# tastatur.net
KiCad netlist of a schematic drawn in EAGLE
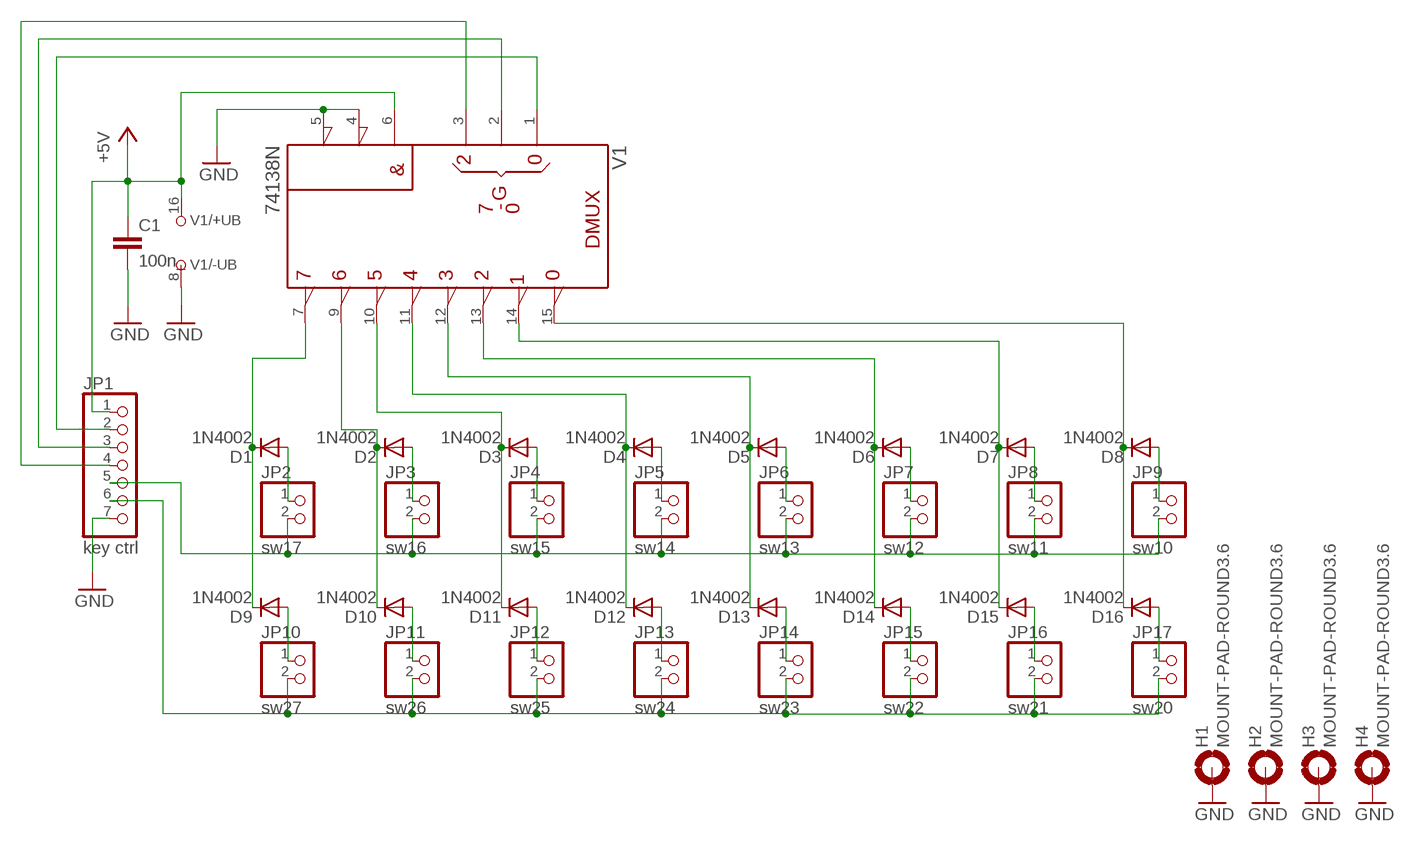
[diagram p0: schematic, sheet 1]

(export (version "E")
  (design (tool "Eeschema 10.0.6"))
  (components
    (comp (ref "C1")
      (value "100n")
      (footprint "eagle-import:C050-024X044")
      (libsource (lib "eagle-import") (part "C-EU050-024X044"))
    )
    (comp (ref "D1")
      (value "1N4002")
      (footprint "eagle-import:DO41-7.6")
      (libsource (lib "eagle-import") (part "1N4002"))
    )
    (comp (ref "D2")
      (value "1N4002")
      (footprint "eagle-import:DO41-7.6")
      (libsource (lib "eagle-import") (part "1N4002"))
    )
    (comp (ref "D3")
      (value "1N4002")
      (footprint "eagle-import:DO41-7.6")
      (libsource (lib "eagle-import") (part "1N4002"))
    )
    (comp (ref "D4")
      (value "1N4002")
      (footprint "eagle-import:DO41-7.6")
      (libsource (lib "eagle-import") (part "1N4002"))
    )
    (comp (ref "D5")
      (value "1N4002")
      (footprint "eagle-import:DO41-7.6")
      (libsource (lib "eagle-import") (part "1N4002"))
    )
    (comp (ref "D6")
      (value "1N4002")
      (footprint "eagle-import:DO41-7.6")
      (libsource (lib "eagle-import") (part "1N4002"))
    )
    (comp (ref "D7")
      (value "1N4002")
      (footprint "eagle-import:DO41-7.6")
      (libsource (lib "eagle-import") (part "1N4002"))
    )
    (comp (ref "D8")
      (value "1N4002")
      (footprint "eagle-import:DO41-7.6")
      (libsource (lib "eagle-import") (part "1N4002"))
    )
    (comp (ref "D9")
      (value "1N4002")
      (footprint "eagle-import:DO41-7.6")
      (libsource (lib "eagle-import") (part "1N4002"))
    )
    (comp (ref "D10")
      (value "1N4002")
      (footprint "eagle-import:DO41-7.6")
      (libsource (lib "eagle-import") (part "1N4002"))
    )
    (comp (ref "D11")
      (value "1N4002")
      (footprint "eagle-import:DO41-7.6")
      (libsource (lib "eagle-import") (part "1N4002"))
    )
    (comp (ref "D12")
      (value "1N4002")
      (footprint "eagle-import:DO41-7.6")
      (libsource (lib "eagle-import") (part "1N4002"))
    )
    (comp (ref "D13")
      (value "1N4002")
      (footprint "eagle-import:DO41-7.6")
      (libsource (lib "eagle-import") (part "1N4002"))
    )
    (comp (ref "D14")
      (value "1N4002")
      (footprint "eagle-import:DO41-7.6")
      (libsource (lib "eagle-import") (part "1N4002"))
    )
    (comp (ref "D15")
      (value "1N4002")
      (footprint "eagle-import:DO41-7.6")
      (libsource (lib "eagle-import") (part "1N4002"))
    )
    (comp (ref "D16")
      (value "1N4002")
      (footprint "eagle-import:DO41-7.6")
      (libsource (lib "eagle-import") (part "1N4002"))
    )
    (comp (ref "H1")
      (value "MOUNT-PAD-ROUND3.6")
      (footprint "eagle-import:3,6-PAD")
      (libsource (lib "eagle-import") (part "MOUNT-PAD-ROUND3.6"))
    )
    (comp (ref "H2")
      (value "MOUNT-PAD-ROUND3.6")
      (footprint "eagle-import:3,6-PAD")
      (libsource (lib "eagle-import") (part "MOUNT-PAD-ROUND3.6"))
    )
    (comp (ref "H3")
      (value "MOUNT-PAD-ROUND3.6")
      (footprint "eagle-import:3,6-PAD")
      (libsource (lib "eagle-import") (part "MOUNT-PAD-ROUND3.6"))
    )
    (comp (ref "H4")
      (value "MOUNT-PAD-ROUND3.6")
      (footprint "eagle-import:3,6-PAD")
      (libsource (lib "eagle-import") (part "MOUNT-PAD-ROUND3.6"))
    )
    (comp (ref "JP1")
      (value "key ctrl")
      (footprint "eagle-import:1X07")
      (libsource (lib "eagle-import") (part "PINHD-1X7"))
    )
    (comp (ref "JP2")
      (value "sw17")
      (footprint "eagle-import:1X02")
      (libsource (lib "eagle-import") (part "PINHD-1X2"))
    )
    (comp (ref "JP3")
      (value "sw16")
      (footprint "eagle-import:1X02")
      (libsource (lib "eagle-import") (part "PINHD-1X2"))
    )
    (comp (ref "JP4")
      (value "sw15")
      (footprint "eagle-import:1X02")
      (libsource (lib "eagle-import") (part "PINHD-1X2"))
    )
    (comp (ref "JP5")
      (value "sw14")
      (footprint "eagle-import:1X02")
      (libsource (lib "eagle-import") (part "PINHD-1X2"))
    )
    (comp (ref "JP6")
      (value "sw13")
      (footprint "eagle-import:1X02")
      (libsource (lib "eagle-import") (part "PINHD-1X2"))
    )
    (comp (ref "JP7")
      (value "sw12")
      (footprint "eagle-import:1X02")
      (libsource (lib "eagle-import") (part "PINHD-1X2"))
    )
    (comp (ref "JP8")
      (value "sw11")
      (footprint "eagle-import:1X02")
      (libsource (lib "eagle-import") (part "PINHD-1X2"))
    )
    (comp (ref "JP9")
      (value "sw10")
      (footprint "eagle-import:1X02")
      (libsource (lib "eagle-import") (part "PINHD-1X2"))
    )
    (comp (ref "JP10")
      (value "sw27")
      (footprint "eagle-import:1X02")
      (libsource (lib "eagle-import") (part "PINHD-1X2"))
    )
    (comp (ref "JP11")
      (value "sw26")
      (footprint "eagle-import:1X02")
      (libsource (lib "eagle-import") (part "PINHD-1X2"))
    )
    (comp (ref "JP12")
      (value "sw25")
      (footprint "eagle-import:1X02")
      (libsource (lib "eagle-import") (part "PINHD-1X2"))
    )
    (comp (ref "JP13")
      (value "sw24")
      (footprint "eagle-import:1X02")
      (libsource (lib "eagle-import") (part "PINHD-1X2"))
    )
    (comp (ref "JP14")
      (value "sw23")
      (footprint "eagle-import:1X02")
      (libsource (lib "eagle-import") (part "PINHD-1X2"))
    )
    (comp (ref "JP15")
      (value "sw22")
      (footprint "eagle-import:1X02")
      (libsource (lib "eagle-import") (part "PINHD-1X2"))
    )
    (comp (ref "JP16")
      (value "sw21")
      (footprint "eagle-import:1X02")
      (libsource (lib "eagle-import") (part "PINHD-1X2"))
    )
    (comp (ref "JP17")
      (value "sw20")
      (footprint "eagle-import:1X02")
      (libsource (lib "eagle-import") (part "PINHD-1X2"))
    )
    (comp (ref "V1")
      (value "74138N")
      (footprint "eagle-import:DIL16")
      (libsource (lib "eagle-import") (part "74138N"))
    )
  )
  (nets
    (net (code "1") (name "+5V") (class "Default")
      (node (ref "C1") (pin "1") (pinfunction "1_1") (pintype "passive"))
      (node (ref "JP1") (pin "1") (pinfunction "1_1") (pintype "passive"))
      (node (ref "V1") (pin "16") (pinfunction "+UB_16") (pintype "power_in"))
      (node (ref "V1") (pin "6") (pinfunction "G1_6") (pintype "input"))
    )
    (net (code "2") (name "GND") (class "Default")
      (node (ref "C1") (pin "2") (pinfunction "2_2") (pintype "passive"))
      (node (ref "H1") (pin "B3,6") (pinfunction "MOUNT_B3,6") (pintype "passive"))
      (node (ref "H2") (pin "B3,6") (pinfunction "MOUNT_B3,6") (pintype "passive"))
      (node (ref "H3") (pin "B3,6") (pinfunction "MOUNT_B3,6") (pintype "passive"))
      (node (ref "H4") (pin "B3,6") (pinfunction "MOUNT_B3,6") (pintype "passive"))
      (node (ref "JP1") (pin "7") (pinfunction "7_7") (pintype "passive"))
      (node (ref "V1") (pin "4") (pinfunction "~{G2A}_4") (pintype "input"))
      (node (ref "V1") (pin "5") (pinfunction "~{G2B}_5") (pintype "input"))
      (node (ref "V1") (pin "8") (pinfunction "-UB_8") (pintype "power_in"))
    )
    (net (code "3") (name "Net-(D1-PadA)") (class "Default")
      (node (ref "D1") (pin "A") (pinfunction "A_A") (pintype "passive"))
      (node (ref "JP2") (pin "1") (pinfunction "1_1") (pintype "passive"))
    )
    (net (code "4") (name "Net-(D2-PadA)") (class "Default")
      (node (ref "D2") (pin "A") (pinfunction "A_A") (pintype "passive"))
      (node (ref "JP3") (pin "1") (pinfunction "1_1") (pintype "passive"))
    )
    (net (code "5") (name "Net-(D3-PadA)") (class "Default")
      (node (ref "D3") (pin "A") (pinfunction "A_A") (pintype "passive"))
      (node (ref "JP4") (pin "1") (pinfunction "1_1") (pintype "passive"))
    )
    (net (code "6") (name "Net-(D4-PadA)") (class "Default")
      (node (ref "D4") (pin "A") (pinfunction "A_A") (pintype "passive"))
      (node (ref "JP5") (pin "1") (pinfunction "1_1") (pintype "passive"))
    )
    (net (code "7") (name "Net-(D5-PadA)") (class "Default")
      (node (ref "D5") (pin "A") (pinfunction "A_A") (pintype "passive"))
      (node (ref "JP6") (pin "1") (pinfunction "1_1") (pintype "passive"))
    )
    (net (code "8") (name "Net-(D6-PadA)") (class "Default")
      (node (ref "D6") (pin "A") (pinfunction "A_A") (pintype "passive"))
      (node (ref "JP7") (pin "1") (pinfunction "1_1") (pintype "passive"))
    )
    (net (code "9") (name "Net-(D7-PadA)") (class "Default")
      (node (ref "D7") (pin "A") (pinfunction "A_A") (pintype "passive"))
      (node (ref "JP8") (pin "1") (pinfunction "1_1") (pintype "passive"))
    )
    (net (code "10") (name "Net-(D8-PadA)") (class "Default")
      (node (ref "D8") (pin "A") (pinfunction "A_A") (pintype "passive"))
      (node (ref "JP9") (pin "1") (pinfunction "1_1") (pintype "passive"))
    )
    (net (code "11") (name "Net-(D9-PadA)") (class "Default")
      (node (ref "D9") (pin "A") (pinfunction "A_A") (pintype "passive"))
      (node (ref "JP10") (pin "1") (pinfunction "1_1") (pintype "passive"))
    )
    (net (code "12") (name "Net-(D10-PadA)") (class "Default")
      (node (ref "D10") (pin "A") (pinfunction "A_A") (pintype "passive"))
      (node (ref "JP11") (pin "1") (pinfunction "1_1") (pintype "passive"))
    )
    (net (code "13") (name "Net-(D11-PadA)") (class "Default")
      (node (ref "D11") (pin "A") (pinfunction "A_A") (pintype "passive"))
      (node (ref "JP12") (pin "1") (pinfunction "1_1") (pintype "passive"))
    )
    (net (code "14") (name "Net-(D12-PadA)") (class "Default")
      (node (ref "D12") (pin "A") (pinfunction "A_A") (pintype "passive"))
      (node (ref "JP13") (pin "1") (pinfunction "1_1") (pintype "passive"))
    )
    (net (code "15") (name "Net-(D13-PadA)") (class "Default")
      (node (ref "D13") (pin "A") (pinfunction "A_A") (pintype "passive"))
      (node (ref "JP14") (pin "1") (pinfunction "1_1") (pintype "passive"))
    )
    (net (code "16") (name "Net-(D14-PadA)") (class "Default")
      (node (ref "D14") (pin "A") (pinfunction "A_A") (pintype "passive"))
      (node (ref "JP15") (pin "1") (pinfunction "1_1") (pintype "passive"))
    )
    (net (code "17") (name "Net-(D15-PadA)") (class "Default")
      (node (ref "D15") (pin "A") (pinfunction "A_A") (pintype "passive"))
      (node (ref "JP16") (pin "1") (pinfunction "1_1") (pintype "passive"))
    )
    (net (code "18") (name "Net-(D16-PadA)") (class "Default")
      (node (ref "D16") (pin "A") (pinfunction "A_A") (pintype "passive"))
      (node (ref "JP17") (pin "1") (pinfunction "1_1") (pintype "passive"))
    )
    (net (code "19") (name "Net-(JP1-Pad5)") (class "Default")
      (node (ref "JP1") (pin "5") (pinfunction "5_5") (pintype "passive"))
      (node (ref "JP2") (pin "2") (pinfunction "2_2") (pintype "passive"))
      (node (ref "JP3") (pin "2") (pinfunction "2_2") (pintype "passive"))
      (node (ref "JP4") (pin "2") (pinfunction "2_2") (pintype "passive"))
      (node (ref "JP5") (pin "2") (pinfunction "2_2") (pintype "passive"))
      (node (ref "JP6") (pin "2") (pinfunction "2_2") (pintype "passive"))
      (node (ref "JP7") (pin "2") (pinfunction "2_2") (pintype "passive"))
      (node (ref "JP8") (pin "2") (pinfunction "2_2") (pintype "passive"))
      (node (ref "JP9") (pin "2") (pinfunction "2_2") (pintype "passive"))
    )
    (net (code "20") (name "Net-(JP1-Pad6)") (class "Default")
      (node (ref "JP1") (pin "6") (pinfunction "6_6") (pintype "passive"))
      (node (ref "JP10") (pin "2") (pinfunction "2_2") (pintype "passive"))
      (node (ref "JP11") (pin "2") (pinfunction "2_2") (pintype "passive"))
      (node (ref "JP12") (pin "2") (pinfunction "2_2") (pintype "passive"))
      (node (ref "JP13") (pin "2") (pinfunction "2_2") (pintype "passive"))
      (node (ref "JP14") (pin "2") (pinfunction "2_2") (pintype "passive"))
      (node (ref "JP15") (pin "2") (pinfunction "2_2") (pintype "passive"))
      (node (ref "JP16") (pin "2") (pinfunction "2_2") (pintype "passive"))
      (node (ref "JP17") (pin "2") (pinfunction "2_2") (pintype "passive"))
    )
    (net (code "21") (name "Net-(V1C-A)") (class "Default")
      (node (ref "JP1") (pin "2") (pinfunction "2_2") (pintype "passive"))
      (node (ref "V1") (pin "1") (pinfunction "A_1") (pintype "input"))
    )
    (net (code "22") (name "Net-(V1C-B)") (class "Default")
      (node (ref "JP1") (pin "3") (pinfunction "3_3") (pintype "passive"))
      (node (ref "V1") (pin "2") (pinfunction "B_2") (pintype "input"))
    )
    (net (code "23") (name "Net-(V1C-C)") (class "Default")
      (node (ref "JP1") (pin "4") (pinfunction "4_4") (pintype "passive"))
      (node (ref "V1") (pin "3") (pinfunction "C_3") (pintype "input"))
    )
    (net (code "24") (name "Net-(V1C-Y0)") (class "Default")
      (node (ref "D16") (pin "C") (pinfunction "C_C") (pintype "passive"))
      (node (ref "D8") (pin "C") (pinfunction "C_C") (pintype "passive"))
      (node (ref "V1") (pin "15") (pinfunction "Y0_15") (pintype "output"))
    )
    (net (code "25") (name "Net-(V1C-Y1)") (class "Default")
      (node (ref "D15") (pin "C") (pinfunction "C_C") (pintype "passive"))
      (node (ref "D7") (pin "C") (pinfunction "C_C") (pintype "passive"))
      (node (ref "V1") (pin "14") (pinfunction "Y1_14") (pintype "output"))
    )
    (net (code "26") (name "Net-(V1C-Y2)") (class "Default")
      (node (ref "D14") (pin "C") (pinfunction "C_C") (pintype "passive"))
      (node (ref "D6") (pin "C") (pinfunction "C_C") (pintype "passive"))
      (node (ref "V1") (pin "13") (pinfunction "Y2_13") (pintype "output"))
    )
    (net (code "27") (name "Net-(V1C-Y3)") (class "Default")
      (node (ref "D13") (pin "C") (pinfunction "C_C") (pintype "passive"))
      (node (ref "D5") (pin "C") (pinfunction "C_C") (pintype "passive"))
      (node (ref "V1") (pin "12") (pinfunction "Y3_12") (pintype "output"))
    )
    (net (code "28") (name "Net-(V1C-Y4)") (class "Default")
      (node (ref "D12") (pin "C") (pinfunction "C_C") (pintype "passive"))
      (node (ref "D4") (pin "C") (pinfunction "C_C") (pintype "passive"))
      (node (ref "V1") (pin "11") (pinfunction "Y4_11") (pintype "output"))
    )
    (net (code "29") (name "Net-(V1C-Y5)") (class "Default")
      (node (ref "D11") (pin "C") (pinfunction "C_C") (pintype "passive"))
      (node (ref "D3") (pin "C") (pinfunction "C_C") (pintype "passive"))
      (node (ref "V1") (pin "10") (pinfunction "Y5_10") (pintype "output"))
    )
    (net (code "30") (name "Net-(V1C-Y6)") (class "Default")
      (node (ref "D10") (pin "C") (pinfunction "C_C") (pintype "passive"))
      (node (ref "D2") (pin "C") (pinfunction "C_C") (pintype "passive"))
      (node (ref "V1") (pin "9") (pinfunction "Y6_9") (pintype "output"))
    )
    (net (code "31") (name "Net-(V1C-Y7)") (class "Default")
      (node (ref "D1") (pin "C") (pinfunction "C_C") (pintype "passive"))
      (node (ref "D9") (pin "C") (pinfunction "C_C") (pintype "passive"))
      (node (ref "V1") (pin "7") (pinfunction "Y7_7") (pintype "output"))
    )
  )
)
